# LTE_auto_start_Rev01.net
KiCad netlist of a schematic drawn in Altium Designer
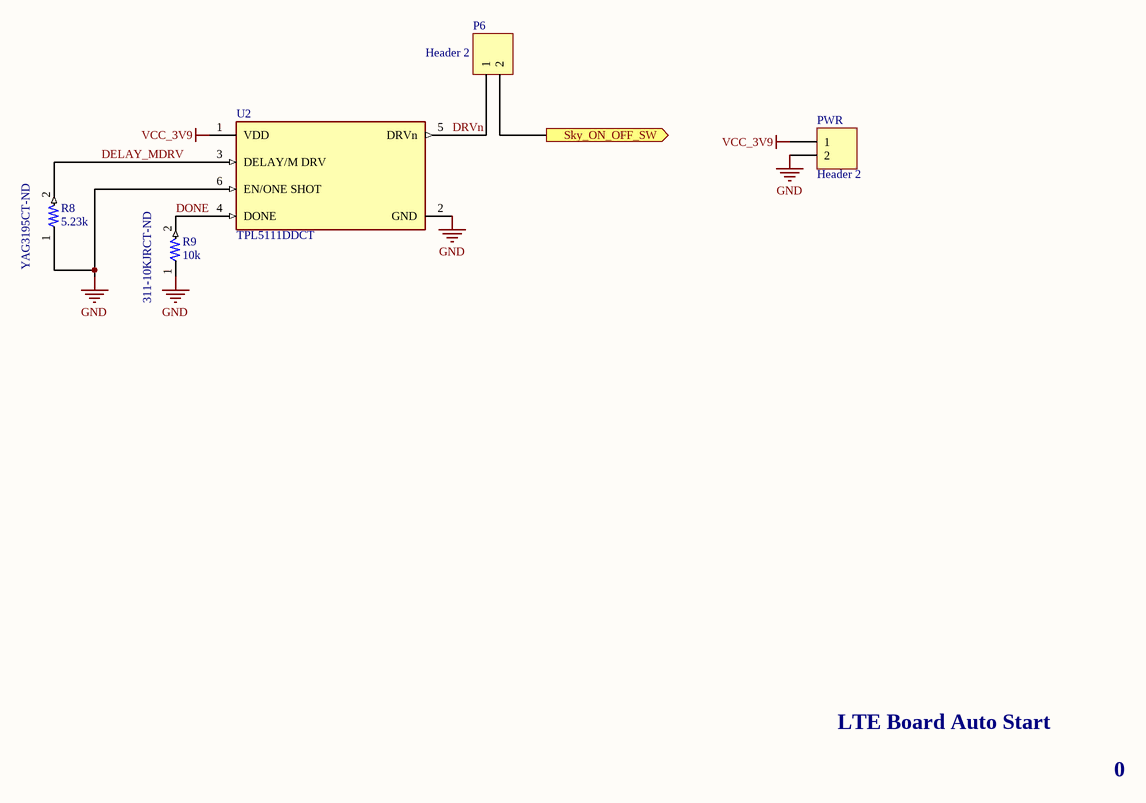
[diagram p0: LTE_auto_start_Rev01.SchDoc]

(export (version "E")
  (design (tool "Eeschema 10.0.6"))
  (components
    (comp (ref "P6")
      (value "Header 2")
      (footprint "HDR1X2")
      (description "Header, 2-Pin")
      (fields (field (name "PUBLISHER") "Altium Limited"))
      (libsource (lib "") (part "Header 2_1"))
    )
    (comp (ref "PWR")
      (value "Header 2")
      (footprint "Wire_entry_200mil")
      (description "Header, 2-Pin")
      (fields (field (name "PUBLISHER") "Altium Limited"))
      (libsource (lib "Miscellaneous Connectors") (part "Header 2"))
    )
    (comp (ref "R8")
      (value "YAG3195CT-ND")
      (footprint "SMD RES 1005")
      (description "5.23 kOhms ±1% 0.063W, 1/16W Chip Resistor 0402 (1005 Metric) Moisture Resistant Thick Film")
      (fields
        (field (name "PART_NUMBER") "YAG3195CT-ND")
        (field (name "RESISTANCE_OHMS") "5.23k")
        (field (name "POWER") "0.063W, 1/16W")
        (field (name "TOLERANCE") "±1%")
      )
      (libsource (lib "AltiumProductionDatabase") (part "R, 1K, 1%, 1/16W, 0402"))
    )
    (comp (ref "R9")
      (value "RC0402JR-0710KL")
      (footprint "SMD RES 1005")
      (description "10 kOhms ±5% 0.063W, 1/16W Chip Resistor 0402 (1005 Metric) Moisture Resistant Thick Film")
      (fields
        (field (name "PART_NUMBER") "311-10KJRCT-ND")
        (field (name "RESISTANCE_OHMS") "10k")
        (field (name "POWER") "0.063W, 1/16W")
        (field (name "TOLERANCE") "±1%")
      )
      (libsource (lib "AltiumProductionDatabase") (part "R, 1K, 1%, 1/16W, 0402"))
    )
    (comp (ref "U2")
      (value "TPL5111DDCT")
      (footprint "FP-DDC0006A-IPC_B")
      (description "IC OSC PROG TIMER TSOT23-6")
      (fields
        (field (name "DIGI-KEY PART NUMBER") "296-42621-1-ND")
        (field (name "MANUFACTURER") "Texas Instruments")
      )
      (libsource (lib "Altium Content Vault") (part "b762ea427669d011917c02059d2a29e"))
    )
  )
  (nets
    (net (code "1") (name "/DELAY_MDRV") (class "Default")
      (node (ref "R8") (pin "2") (pinfunction "2_2") (pintype "output"))
      (node (ref "U2") (pin "3") (pinfunction "DELAY/M_DRV_3") (pintype "input"))
    )
    (net (code "2") (name "/DONE") (class "Default")
      (node (ref "R9") (pin "2") (pinfunction "2_2") (pintype "output"))
      (node (ref "U2") (pin "4") (pinfunction "DONE_4") (pintype "input"))
    )
    (net (code "3") (name "/DRVn") (class "Default")
      (node (ref "P6") (pin "1") (pinfunction "1_1") (pintype "passive"))
      (node (ref "U2") (pin "5") (pinfunction "DRVn_5") (pintype "output"))
    )
    (net (code "4") (name "/Sky_ON_OFF_SW") (class "Default")
      (node (ref "P6") (pin "2") (pinfunction "2_2") (pintype "passive"))
    )
    (net (code "5") (name "GND") (class "Default")
      (node (ref "PWR") (pin "2") (pinfunction "2_2") (pintype "passive"))
      (node (ref "R8") (pin "1") (pinfunction "1_1") (pintype "passive"))
      (node (ref "R9") (pin "1") (pinfunction "1_1") (pintype "passive"))
      (node (ref "U2") (pin "2") (pinfunction "GND_2") (pintype "power_in"))
      (node (ref "U2") (pin "6") (pinfunction "EN/ONE_SHOT_6") (pintype "input"))
    )
    (net (code "6") (name "VCC_3V9") (class "Default")
      (node (ref "PWR") (pin "1") (pinfunction "1_1") (pintype "passive"))
      (node (ref "U2") (pin "1") (pinfunction "VDD_1") (pintype "power_in"))
    )
  )
)
